# MCU.net
KiCad netlist of a schematic drawn in Altium Designer
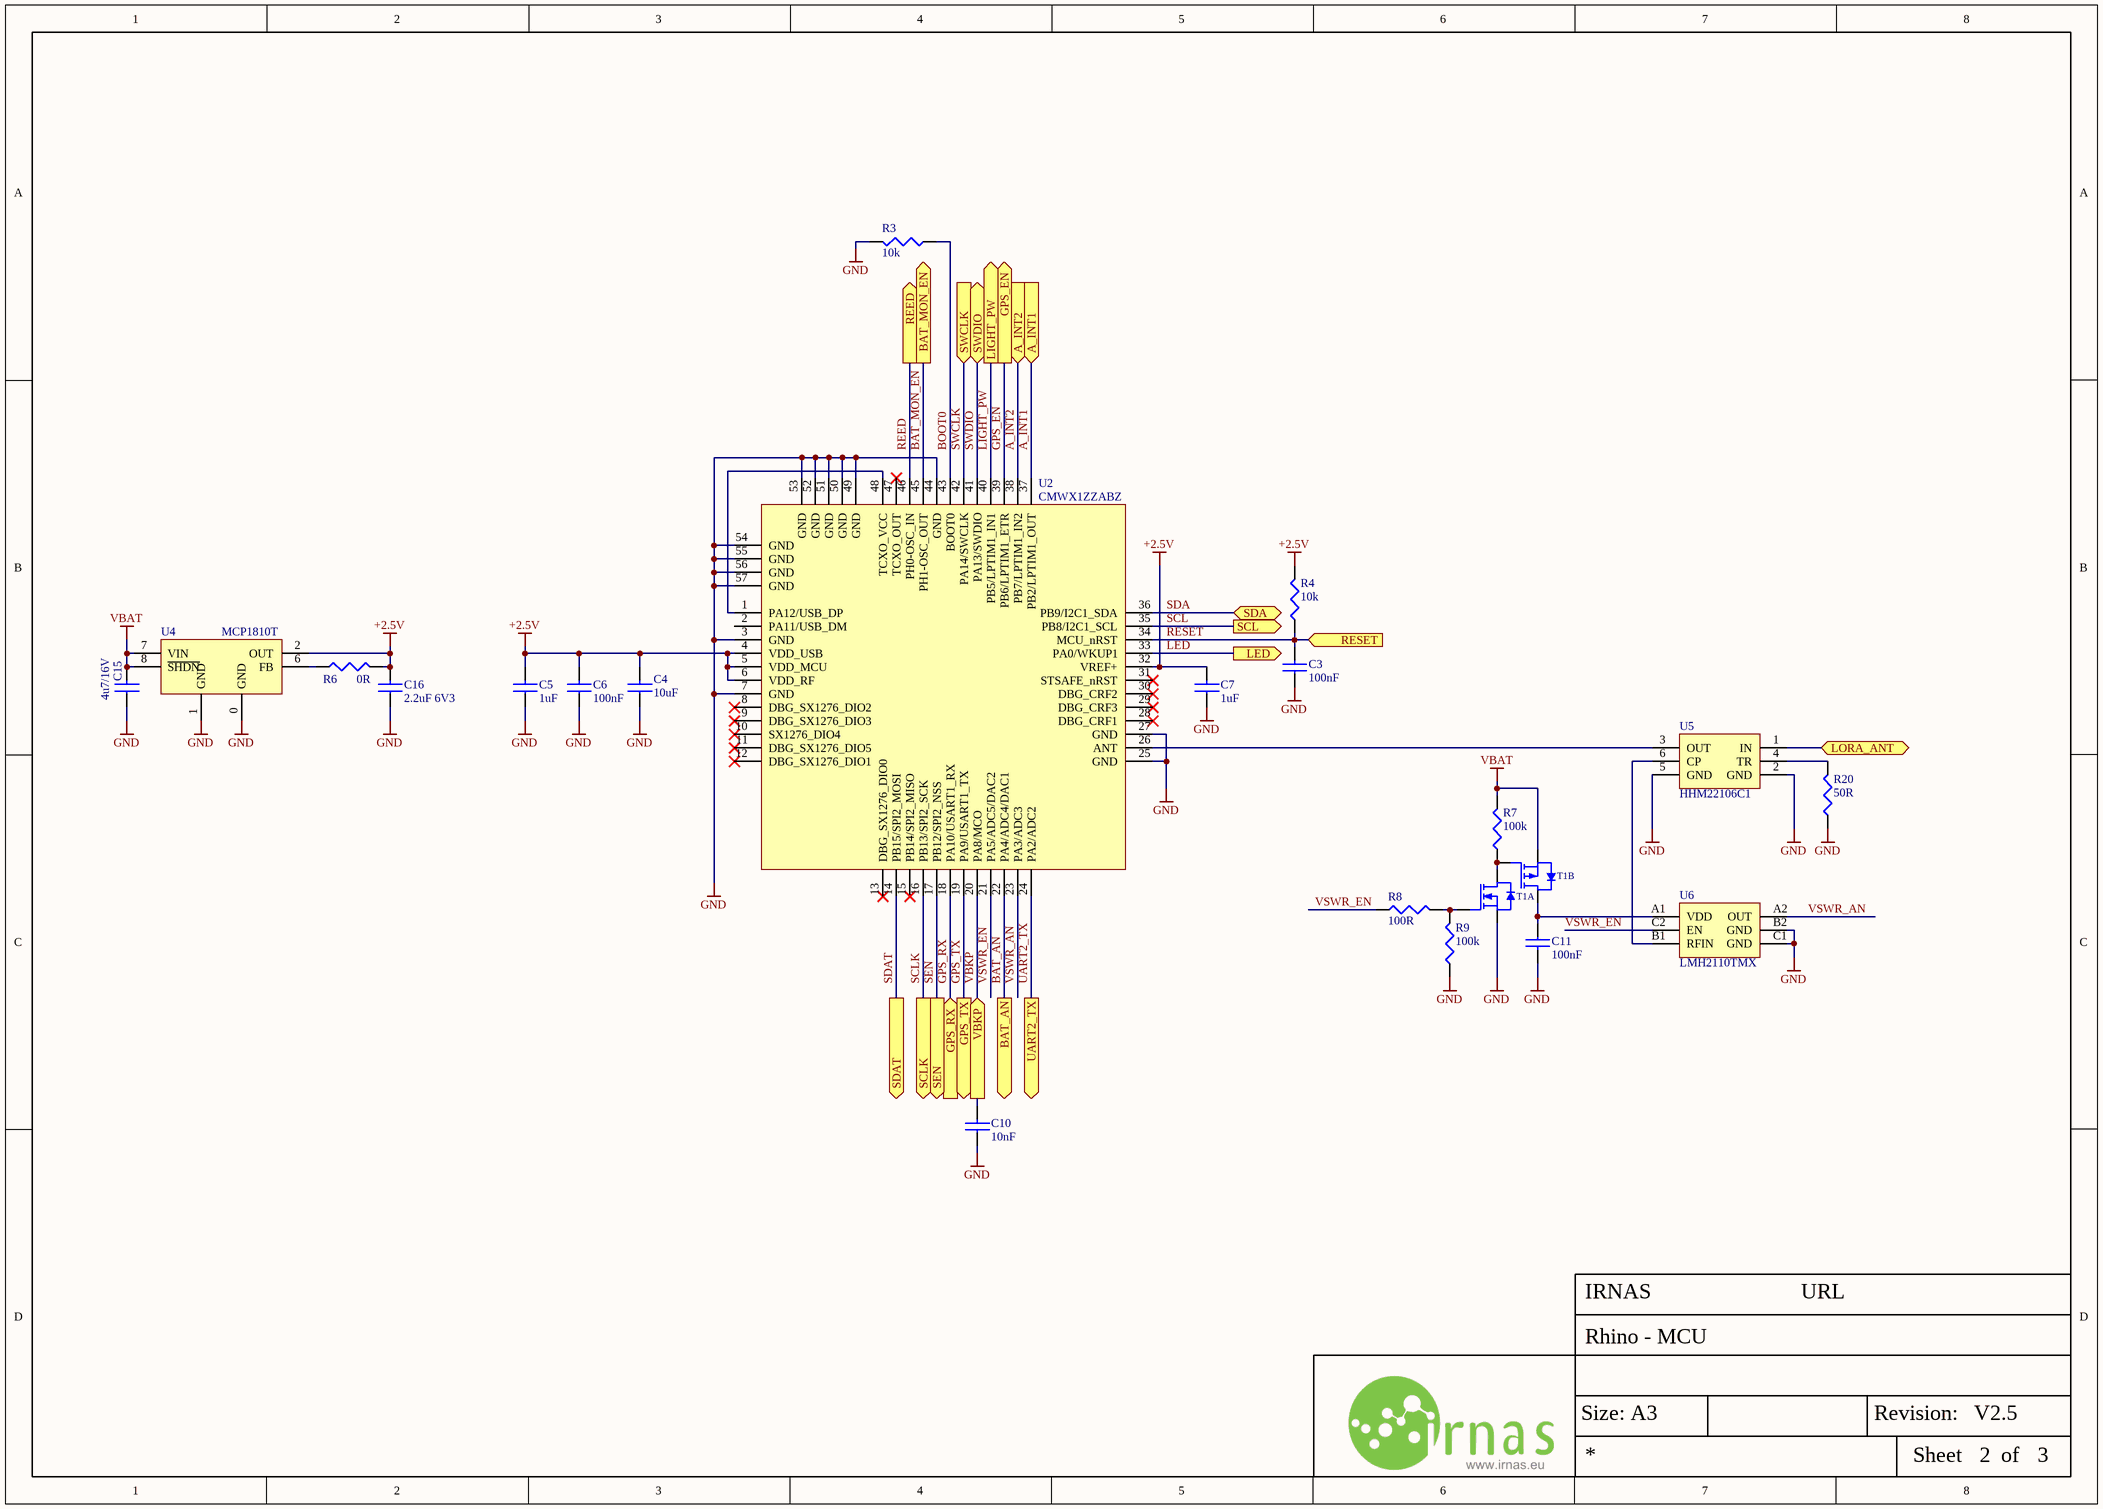
[diagram p0: MCU.SchDoc]

(export (version "E")
  (design (tool "Eeschema 10.0.6"))
  (components
    (comp (ref "C3")
      (value "100nF")
      (footprint "CAP0402")
      (fields
        (field (name "MANUFACTURER") "Multicomp")
        (field (name "MANUFACTURER PART NUMBER") "MC0402X104J160CT")
        (field (name "TOLERANCE") "5%")
      )
      (libsource (lib "Passive") (part "C - 100nF/0402"))
    )
    (comp (ref "C4")
      (value "10uF")
      (footprint "CAP0603")
      (description "10uf/0603/20%")
      (fields
        (field (name "MANUFACTURER") "KEMET")
        (field (name "MANUFACTURER PART NUMBER") "C0603C106M8PACTU")
      )
      (libsource (lib "pira-smart-schlib") (part "10uF"))
    )
    (comp (ref "C5")
      (value "1uF")
      (footprint "CAP0402")
      (description "CAP CER 1UF 10V 20% X5R 0402")
      (fields
        (field (name "MANUFACTURER") "Murata")
        (field (name "MANUFACTURER PART NUMBER") "GRM155R61A105ME15D")
      )
      (libsource (lib "Passive") (part "C - 1uF/0402"))
    )
    (comp (ref "C6")
      (value "100nF")
      (footprint "CAP0402")
      (fields
        (field (name "MANUFACTURER") "Multicomp")
        (field (name "MANUFACTURER PART NUMBER") "MC0402X104J160CT")
        (field (name "TOLERANCE") "5%")
      )
      (libsource (lib "Passive") (part "C - 100nF/0402"))
    )
    (comp (ref "C7")
      (value "1uF")
      (footprint "CAP0402")
      (description "CAP CER 1UF 10V 20% X5R 0402")
      (fields
        (field (name "MANUFACTURER") "Murata")
        (field (name "MANUFACTURER PART NUMBER") "GRM155R61A105ME15D")
      )
      (libsource (lib "Passive") (part "C - 1uF/0402"))
    )
    (comp (ref "C10")
      (value "10nF")
      (footprint "CAP0402")
      (description "CAP CER 10000PF 16V X7R 0402")
      (fields
        (field (name "MANUFACTURER") "Murata")
        (field (name "MANUFACTURER PART NUMBER") "GRM155R71C103KA01D")
      )
      (libsource (lib "Passive") (part "C - 10nF/0402"))
    )
    (comp (ref "C11")
      (value "100nF")
      (footprint "CAP0402")
      (fields
        (field (name "MANUFACTURER") "Multicomp")
        (field (name "MANUFACTURER PART NUMBER") "MC0402X104J160CT")
        (field (name "TOLERANCE") "5%")
      )
      (libsource (lib "Passive") (part "C - 100nF/0402"))
    )
    (comp (ref "C15")
      (value "4u7/16V")
      (footprint "CAP0603")
      (description "MURATA - GRM188R61C475KAAJD - CAP, MLCC, X5R, 4.7UF, 16V, 0603")
      (fields
        (field (name "MANUFACTURER") "MURATA")
        (field (name "MANUFACTURER PART NUMBER") "GRM188R61C475KAAJD")
      )
      (libsource (lib "Passive") (part "C - 4u7  16V 0603"))
    )
    (comp (ref "C16")
      (value "2.2uF 6V3")
      (footprint "CAP0402")
      (description "CAP CER 2.2UF 6.3V 20% X5R 0402")
      (fields
        (field (name "MANUFACTURER") "Murata")
        (field (name "MANUFACTURER PART NUMBER") "GRM155R60J225ME15D")
      )
      (libsource (lib "Passive") (part "C - 2.2uF/6V3/0402"))
    )
    (comp (ref "R3")
      (value "10k")
      (footprint "RES0402")
      (fields
        (field (name "MANUFACTURER") "Multicomp")
        (field (name "MANUFACTURER PART NUMBER") "MCWR04X1002FTL")
        (field (name "TOLERANCE") "1%")
      )
      (libsource (lib "Passive") (part "R - 10k/0402"))
    )
    (comp (ref "R4")
      (value "10k")
      (footprint "RES0402")
      (fields
        (field (name "MANUFACTURER") "Multicomp")
        (field (name "MANUFACTURER PART NUMBER") "MCWR04X1002FTL")
        (field (name "TOLERANCE") "1%")
      )
      (libsource (lib "Passive") (part "R - 10k/0402"))
    )
    (comp (ref "R6")
      (value "0R")
      (footprint "RES0402")
      (description "RESISTOR, 0402, 0R, ANTI SULFURATION")
      (fields
        (field (name "MANUFACTURER") "Multicomp")
        (field (name "MANUFACTURER PART NUMBER") "MCMR04X000PTL")
      )
      (libsource (lib "Passive") (part "R - 0R/0402"))
    )
    (comp (ref "R7")
      (value "100k")
      (footprint "RES0402")
      (description "MULTICOMP   MCWR04X1003FTL   RES, THICK FILM, 100KOHM, 1%, 0.0625W")
      (fields
        (field (name "MANUFACTURER") "Multicomp")
        (field (name "MANUFACTURER PART NUMBER") "MCWR04X1003FTL")
      )
      (libsource (lib "Passive") (part "R - 100k/0402"))
    )
    (comp (ref "R8")
      (value "100R")
      (footprint "RES0402")
      (fields
        (field (name "MANUFACTURER") "Multicomp")
        (field (name "MANUFACTURER PART NUMBER") "MCMR04X1000FTL")
        (field (name "TOLERANCE") "1%")
      )
      (libsource (lib "Passive") (part "R - 100R/0402"))
    )
    (comp (ref "R9")
      (value "100k")
      (footprint "RES0402")
      (description "MULTICOMP   MCWR04X1003FTL   RES, THICK FILM, 100KOHM, 1%, 0.0625W")
      (fields
        (field (name "MANUFACTURER") "Multicomp")
        (field (name "MANUFACTURER PART NUMBER") "MCWR04X1003FTL")
      )
      (libsource (lib "Passive") (part "R - 100k/0402"))
    )
    (comp (ref "R20")
      (value "50R")
      (footprint "RES0402")
      (description "SMD Chip Resistor, 0402 [1005 Metric], 50 ohm, FC Series, 30 V, Thin Film, 50 mW")
      (fields
        (field (name "MANUFACTURER") "Vishay")
        (field (name "MANUFACTURER PART NUMBER") "CRCW060351R0FKEA")
      )
      (libsource (lib "Passive") (part "R - 50R"))
    )
    (comp (ref "T1")
      (value "VT6M1T2CR")
      (footprint "VMT6")
      (description "Dual MOSFET, N and P Channel, 100 mA, 20 V, 2.5 ohm, 4.5 V, 1 V")
      (fields (field (name "AUTHOR") "Ciril Golob"))
      (libsource (lib "Active") (part "T_M - VT6M1T2CR"))
    )
    (comp (ref "U2")
      (value "CMWX1ZZABZ")
      (footprint "Lora Module ES0")
      (description "RF Module, FSK, OOK, LoRa, 4.8Kbps, 915MHz, -135.5dBm, 2.2V to 3.6V, I2C, SPI, UART, USB")
      (fields
        (field (name "MANUFACTURER") "Murata")
        (field (name "MANUFACTURER PART NUMBER") "CMWX1ZZABZ-091")
      )
      (libsource (lib "Active") (part "MCU - CMWX1ZZABZ"))
    )
    (comp (ref "U4")
      (value "MCP1810T")
      (footprint "VDFN_2x2")
      (description "LDO Voltage Regulator, Fixed, 2.5 V to 5.5 V in, 2.5 V/150 mA out, 380 mV drop")
      (fields
        (field (name "MANUFACTURER") "ON SEMICONDUCTOR")
        (field (name "MANUFACTURER PART NUMBER") "LM2596DSADJG")
      )
      (libsource (lib "Active") (part "V_LIN - MCP1810T"))
    )
    (comp (ref "U5")
      (value "HHM22106C1")
      (footprint "HHM22106C1")
      (description "Signal Conditioning DIRECTIONAL COUPLER 700-2700MHz")
      (fields (field (name "MANUFACTURER") "u-blox") (field (name "MANUFACTURER PART NUMBER") "MAX-M8Q-0"))
      (libsource (lib "Active") (part "RF - HHM22106C1"))
    )
    (comp (ref "U6")
      (value "LMH2110TMX")
      (footprint "DSBGA-6")
      (description "RF Detector IC GSM, EDGE, CDMA 50MHz ~ 8GHz -40dBm ~ 5dBm ±0,5dB")
      (fields (field (name "MANUFACTURER") "u-blox") (field (name "MANUFACTURER PART NUMBER") "MAX-M8Q-0"))
      (libsource (lib "Active") (part "RF - LMH2110TMX"))
    )
  )
  (nets
    (net (code "1") (name "+2.5V") (class "Default")
      (node (ref "C16") (pin "2") (pinfunction "2_2") (pintype "passive"))
      (node (ref "C4") (pin "2") (pinfunction "2_2") (pintype "passive"))
      (node (ref "C5") (pin "2") (pinfunction "2_2") (pintype "passive"))
      (node (ref "C6") (pin "2") (pinfunction "2_2") (pintype "passive"))
      (node (ref "C7") (pin "2") (pinfunction "2_2") (pintype "passive"))
      (node (ref "R4") (pin "2") (pinfunction "2_2") (pintype "passive"))
      (node (ref "R6") (pin "2") (pinfunction "2_2") (pintype "passive"))
      (node (ref "U2") (pin "32") (pinfunction "VREF+_32") (pintype "passive"))
      (node (ref "U2") (pin "4") (pinfunction "VDD_USB_4") (pintype "passive"))
      (node (ref "U2") (pin "5") (pinfunction "VDD_MCU_5") (pintype "passive"))
      (node (ref "U2") (pin "6") (pinfunction "VDD_RF_6") (pintype "passive"))
      (node (ref "U4") (pin "2") (pinfunction "OUT_2") (pintype "open_collector"))
    )
    (net (code "2") (name "/A_INT1") (class "Default")
      (node (ref "U2") (pin "37") (pinfunction "PB2/LPTIM1_OUT_37") (pintype "passive"))
    )
    (net (code "3") (name "/A_INT2") (class "Default")
      (node (ref "U2") (pin "38") (pinfunction "PB7/LPTIM1_IN2_38") (pintype "passive"))
    )
    (net (code "4") (name "/BAT_AN") (class "Default")
      (node (ref "U2") (pin "22") (pinfunction "PA4/ADC4/DAC1_22") (pintype "passive"))
    )
    (net (code "5") (name "/BAT_MON_EN") (class "Default")
      (node (ref "U2") (pin "45") (pinfunction "PH1-OSC_OUT_45") (pintype "passive"))
    )
    (net (code "6") (name "/BOOT0") (class "Default")
      (node (ref "R3") (pin "1") (pinfunction "1_1") (pintype "passive"))
      (node (ref "U2") (pin "43") (pinfunction "BOOT0_43") (pintype "passive"))
    )
    (net (code "7") (name "/GPS_EN") (class "Default")
      (node (ref "U2") (pin "39") (pinfunction "PB6/LPTIM1_ETR_39") (pintype "passive"))
    )
    (net (code "8") (name "/GPS_RX") (class "Default")
      (node (ref "U2") (pin "18") (pinfunction "PA10/USART1_RX_18") (pintype "passive"))
    )
    (net (code "9") (name "/GPS_TX") (class "Default")
      (node (ref "U2") (pin "19") (pinfunction "PA9/USART1_TX_19") (pintype "passive"))
    )
    (net (code "10") (name "/LED") (class "Default")
      (node (ref "U2") (pin "33") (pinfunction "PA0/WKUP1_33") (pintype "passive"))
    )
    (net (code "11") (name "/LIGHT_PW") (class "Default")
      (node (ref "U2") (pin "40") (pinfunction "PB5/LPTIM1_IN1_40") (pintype "passive"))
    )
    (net (code "12") (name "/LORA_ANT") (class "Default")
      (node (ref "U5") (pin "1") (pinfunction "IN_1") (pintype "passive"))
    )
    (net (code "13") (name "/REED") (class "Default")
      (node (ref "U2") (pin "46") (pinfunction "PH0-OSC_IN_46") (pintype "passive"))
    )
    (net (code "14") (name "/RESET") (class "Default")
      (node (ref "C3") (pin "2") (pinfunction "2_2") (pintype "passive"))
      (node (ref "R4") (pin "1") (pinfunction "1_1") (pintype "passive"))
      (node (ref "U2") (pin "34") (pinfunction "MCU_nRST_34") (pintype "passive"))
    )
    (net (code "15") (name "/SCL") (class "Default")
      (node (ref "U2") (pin "35") (pinfunction "PB8/I2C1_SCL_35") (pintype "passive"))
    )
    (net (code "16") (name "/SCLK") (class "Default")
      (node (ref "U2") (pin "16") (pinfunction "PB13/SPI2_SCK_16") (pintype "passive"))
    )
    (net (code "17") (name "/SDA") (class "Default")
      (node (ref "U2") (pin "36") (pinfunction "PB9/I2C1_SDA_36") (pintype "passive"))
    )
    (net (code "18") (name "/SDAT") (class "Default")
      (node (ref "U2") (pin "14") (pinfunction "PB15/SPI2_MOSI_14") (pintype "passive"))
    )
    (net (code "19") (name "/SEN") (class "Default")
      (node (ref "U2") (pin "17") (pinfunction "PB12/SPI2_NSS_17") (pintype "passive"))
    )
    (net (code "20") (name "/SWCLK") (class "Default")
      (node (ref "U2") (pin "42") (pinfunction "PA14/SWCLK_42") (pintype "passive"))
    )
    (net (code "21") (name "/SWDIO") (class "Default")
      (node (ref "U2") (pin "41") (pinfunction "PA13/SWDIO_41") (pintype "passive"))
    )
    (net (code "22") (name "/UART2_TX") (class "Default")
      (node (ref "U2") (pin "24") (pinfunction "PA2/ADC2_24") (pintype "passive"))
    )
    (net (code "23") (name "/VBKP") (class "Default")
      (node (ref "C10") (pin "2") (pinfunction "2_2") (pintype "passive"))
      (node (ref "U2") (pin "20") (pinfunction "PA8/MCO_20") (pintype "passive"))
    )
    (net (code "24") (name "/VSWR_AN") (class "Default")
      (node (ref "U2") (pin "23") (pinfunction "PA3/ADC3_23") (pintype "passive"))
      (node (ref "U6") (pin "A2") (pinfunction "OUT_A2") (pintype "passive"))
    )
    (net (code "25") (name "/VSWR_EN") (class "Default")
      (node (ref "R8") (pin "1") (pinfunction "1_1") (pintype "passive"))
      (node (ref "U2") (pin "21") (pinfunction "PA5/ADC5/DAC2_21") (pintype "passive"))
      (node (ref "U6") (pin "C2") (pinfunction "EN_C2") (pintype "passive"))
    )
    (net (code "26") (name "GND") (class "Default")
      (node (ref "C10") (pin "1") (pinfunction "1_1") (pintype "passive"))
      (node (ref "C11") (pin "2") (pinfunction "2_2") (pintype "passive"))
      (node (ref "C15") (pin "1") (pinfunction "1_1") (pintype "passive"))
      (node (ref "C16") (pin "1") (pinfunction "1_1") (pintype "passive"))
      (node (ref "C3") (pin "1") (pinfunction "1_1") (pintype "passive"))
      (node (ref "C4") (pin "1") (pinfunction "1_1") (pintype "passive"))
      (node (ref "C5") (pin "1") (pinfunction "1_1") (pintype "passive"))
      (node (ref "C6") (pin "1") (pinfunction "1_1") (pintype "passive"))
      (node (ref "C7") (pin "1") (pinfunction "1_1") (pintype "passive"))
      (node (ref "R20") (pin "1") (pinfunction "1_1") (pintype "passive"))
      (node (ref "R3") (pin "2") (pinfunction "2_2") (pintype "passive"))
      (node (ref "R9") (pin "1") (pinfunction "1_1") (pintype "passive"))
      (node (ref "T1") (pin "1") (pinfunction "S1_1") (pintype "passive"))
      (node (ref "U2") (pin "25") (pinfunction "GND_25") (pintype "passive"))
      (node (ref "U2") (pin "27") (pinfunction "GND_27") (pintype "passive"))
      (node (ref "U2") (pin "3") (pinfunction "GND_3") (pintype "passive"))
      (node (ref "U2") (pin "44") (pinfunction "GND_44") (pintype "passive"))
      (node (ref "U2") (pin "49") (pinfunction "GND_49") (pintype "passive"))
      (node (ref "U2") (pin "50") (pinfunction "GND_50") (pintype "passive"))
      (node (ref "U2") (pin "51") (pinfunction "GND_51") (pintype "passive"))
      (node (ref "U2") (pin "52") (pinfunction "GND_52") (pintype "passive"))
      (node (ref "U2") (pin "53") (pinfunction "GND_53") (pintype "passive"))
      (node (ref "U2") (pin "54") (pinfunction "GND_54") (pintype "passive"))
      (node (ref "U2") (pin "55") (pinfunction "GND_55") (pintype "passive"))
      (node (ref "U2") (pin "56") (pinfunction "GND_56") (pintype "passive"))
      (node (ref "U2") (pin "57") (pinfunction "GND_57") (pintype "passive"))
      (node (ref "U2") (pin "7") (pinfunction "GND_7") (pintype "passive"))
      (node (ref "U4") (pin "0") (pinfunction "GND_0") (pintype "open_collector"))
      (node (ref "U4") (pin "1") (pinfunction "GND_1") (pintype "open_collector"))
      (node (ref "U5") (pin "2") (pinfunction "GND_2") (pintype "passive"))
      (node (ref "U5") (pin "5") (pinfunction "GND_5") (pintype "passive"))
      (node (ref "U6") (pin "B2") (pinfunction "GND_B2") (pintype "passive"))
      (node (ref "U6") (pin "C1") (pinfunction "GND_C1") (pintype "passive"))
    )
    (net (code "27") (name "Net-(T1A-D1)") (class "Default")
      (node (ref "R7") (pin "1") (pinfunction "1_1") (pintype "passive"))
      (node (ref "T1") (pin "5") (pinfunction "G2_5") (pintype "passive"))
      (node (ref "T1") (pin "6") (pinfunction "D1_6") (pintype "passive"))
    )
    (net (code "28") (name "Net-(T1A-G1)") (class "Default")
      (node (ref "R8") (pin "2") (pinfunction "2_2") (pintype "passive"))
      (node (ref "R9") (pin "2") (pinfunction "2_2") (pintype "passive"))
      (node (ref "T1") (pin "2") (pinfunction "G1_2") (pintype "passive"))
    )
    (net (code "29") (name "Net-(T1B-D2)") (class "Default")
      (node (ref "C11") (pin "1") (pinfunction "1_1") (pintype "passive"))
      (node (ref "T1") (pin "3") (pinfunction "D2_3") (pintype "passive"))
      (node (ref "U6") (pin "A1") (pinfunction "VDD_A1") (pintype "passive"))
    )
    (net (code "30") (name "Net-(U2-ANT)") (class "Default")
      (node (ref "U2") (pin "26") (pinfunction "ANT_26") (pintype "passive"))
      (node (ref "U5") (pin "3") (pinfunction "OUT_3") (pintype "passive"))
    )
    (net (code "31") (name "Net-(U2-PA12{slash}USB_DP)") (class "Default")
      (node (ref "U2") (pin "1") (pinfunction "PA12/USB_DP_1") (pintype "passive"))
      (node (ref "U2") (pin "48") (pinfunction "TCXO_VCC_48") (pintype "passive"))
    )
    (net (code "32") (name "Net-(U4-FB)") (class "Default")
      (node (ref "R6") (pin "1") (pinfunction "1_1") (pintype "passive"))
      (node (ref "U4") (pin "6") (pinfunction "FB_6") (pintype "open_collector"))
    )
    (net (code "33") (name "Net-(U5-CP)") (class "Default")
      (node (ref "U5") (pin "6") (pinfunction "CP_6") (pintype "passive"))
      (node (ref "U6") (pin "B1") (pinfunction "RFIN_B1") (pintype "passive"))
    )
    (net (code "34") (name "Net-(U5-TR)") (class "Default")
      (node (ref "R20") (pin "2") (pinfunction "2_2") (pintype "passive"))
      (node (ref "U5") (pin "4") (pinfunction "TR_4") (pintype "passive"))
    )
    (net (code "35") (name "VBAT") (class "Default")
      (node (ref "C15") (pin "2") (pinfunction "2_2") (pintype "passive"))
      (node (ref "R7") (pin "2") (pinfunction "2_2") (pintype "passive"))
      (node (ref "T1") (pin "4") (pinfunction "S2_4") (pintype "passive"))
      (node (ref "U4") (pin "7") (pinfunction "VIN_7") (pintype "open_collector"))
      (node (ref "U4") (pin "8") (pinfunction "~{SHDN}_8") (pintype "open_collector"))
    )
    (net (code "36") (name "unconnected-(U2-DBG_CRF1-Pad28)") (class "Default")
      (node (ref "U2") (pin "28") (pinfunction "DBG_CRF1_28") (pintype "passive+no_connect"))
    )
    (net (code "37") (name "unconnected-(U2-DBG_CRF2-Pad30)") (class "Default")
      (node (ref "U2") (pin "30") (pinfunction "DBG_CRF2_30") (pintype "passive+no_connect"))
    )
    (net (code "38") (name "unconnected-(U2-DBG_CRF3-Pad29)") (class "Default")
      (node (ref "U2") (pin "29") (pinfunction "DBG_CRF3_29") (pintype "passive+no_connect"))
    )
    (net (code "39") (name "unconnected-(U2-DBG_SX1276_DIO0-Pad13)") (class "Default")
      (node (ref "U2") (pin "13") (pinfunction "DBG_SX1276_DIO0_13") (pintype "passive+no_connect"))
    )
    (net (code "40") (name "unconnected-(U2-DBG_SX1276_DIO1-Pad12)") (class "Default")
      (node (ref "U2") (pin "12") (pinfunction "DBG_SX1276_DIO1_12") (pintype "passive+no_connect"))
    )
    (net (code "41") (name "unconnected-(U2-DBG_SX1276_DIO2-Pad8)") (class "Default")
      (node (ref "U2") (pin "8") (pinfunction "DBG_SX1276_DIO2_8") (pintype "passive+no_connect"))
    )
    (net (code "42") (name "unconnected-(U2-DBG_SX1276_DIO3-Pad9)") (class "Default")
      (node (ref "U2") (pin "9") (pinfunction "DBG_SX1276_DIO3_9") (pintype "passive+no_connect"))
    )
    (net (code "43") (name "unconnected-(U2-DBG_SX1276_DIO5-Pad11)") (class "Default")
      (node (ref "U2") (pin "11") (pinfunction "DBG_SX1276_DIO5_11") (pintype "passive+no_connect"))
    )
    (net (code "44") (name "unconnected-(U2-PA11{slash}USB_DM-Pad2)") (class "Default")
      (node (ref "U2") (pin "2") (pinfunction "PA11/USB_DM_2") (pintype "passive"))
    )
    (net (code "45") (name "unconnected-(U2-PB14{slash}SPI2_MISO-Pad15)") (class "Default")
      (node (ref "U2") (pin "15") (pinfunction "PB14/SPI2_MISO_15") (pintype "passive+no_connect"))
    )
    (net (code "46") (name "unconnected-(U2-STSAFE_nRST-Pad31)") (class "Default")
      (node (ref "U2") (pin "31") (pinfunction "STSAFE_nRST_31") (pintype "passive+no_connect"))
    )
    (net (code "47") (name "unconnected-(U2-SX1276_DIO4-Pad10)") (class "Default")
      (node (ref "U2") (pin "10") (pinfunction "SX1276_DIO4_10") (pintype "passive+no_connect"))
    )
    (net (code "48") (name "unconnected-(U2-TCXO_OUT-Pad47)") (class "Default")
      (node (ref "U2") (pin "47") (pinfunction "TCXO_OUT_47") (pintype "passive+no_connect"))
    )
  )
)
